# 5V.net
KiCad netlist of a schematic drawn in Altium Designer
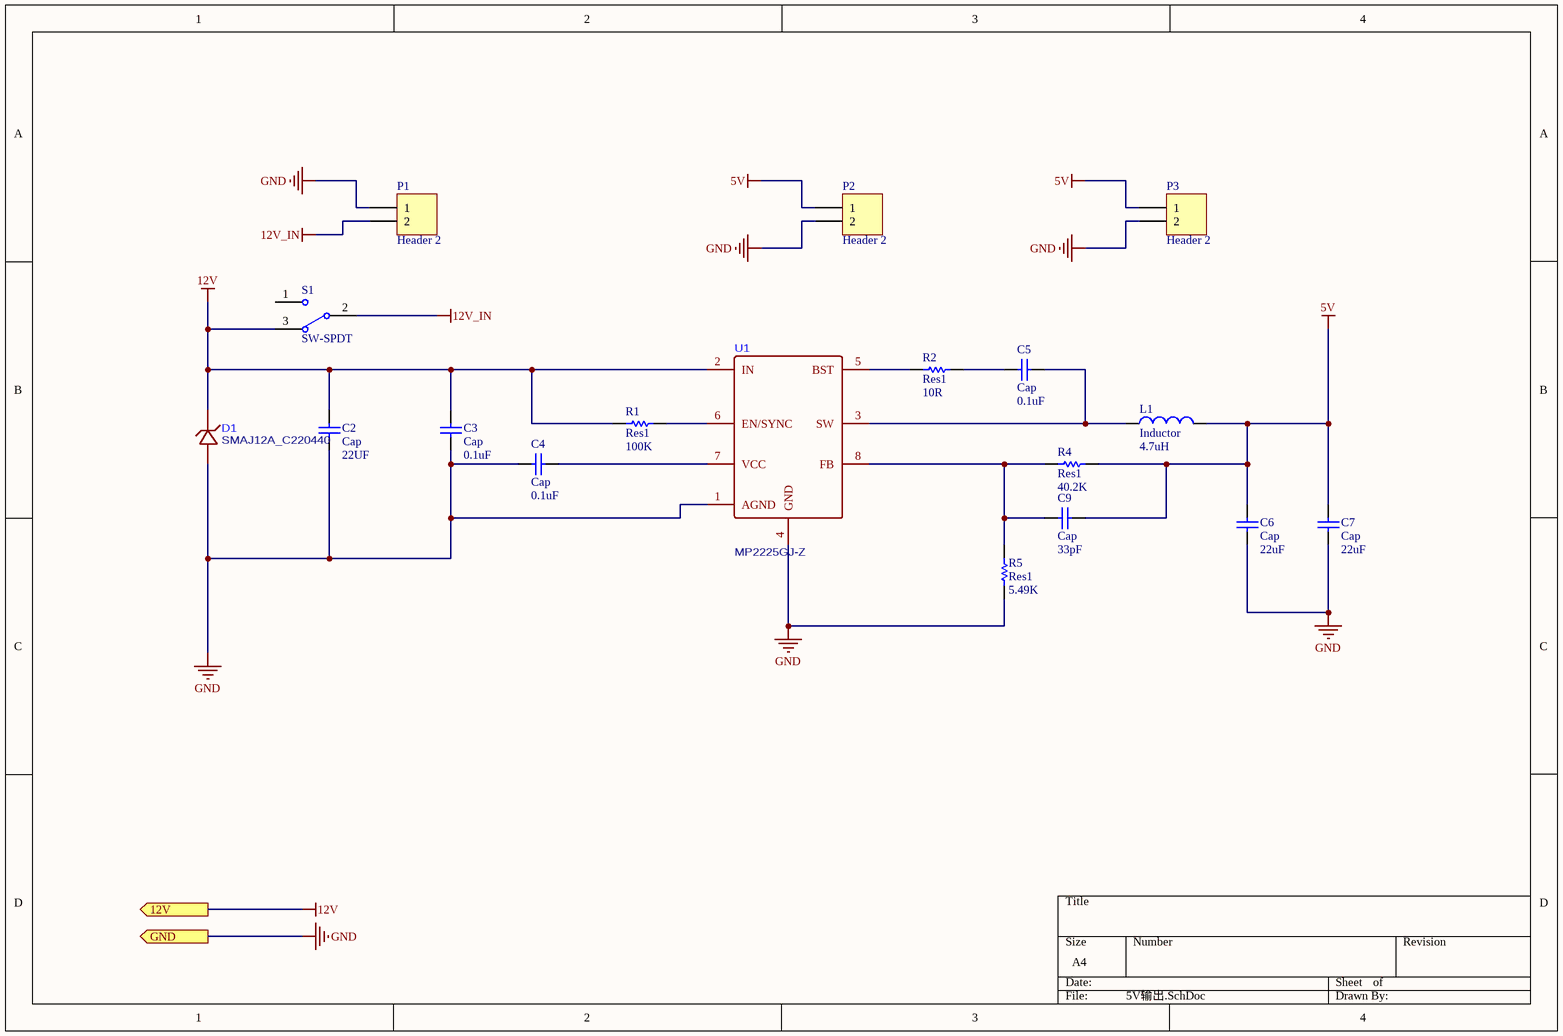
[diagram p0: 5V输出.SchDoc]

(export (version "E")
  (design (tool "Eeschema 10.0.6"))
  (components
    (comp (ref "C2")
      (value "Cap")
      (footprint "C1206")
      (description "Capacitor")
      (fields (field (name "ALTIUM_VALUE") "22UF") (field (name "PUBLISHER") "Altium Limited"))
      (libsource (lib "Miscellaneous Devices") (part "Cap"))
    )
    (comp (ref "C3")
      (value "Cap")
      (footprint "R0603")
      (description "Capacitor")
      (fields (field (name "ALTIUM_VALUE") "0.1uF") (field (name "PUBLISHER") "Altium Limited"))
      (libsource (lib "Miscellaneous Devices") (part "Cap"))
    )
    (comp (ref "C4")
      (value "Cap")
      (footprint "R0603")
      (description "Capacitor")
      (fields (field (name "ALTIUM_VALUE") "0.1uF") (field (name "PUBLISHER") "Altium Limited"))
      (libsource (lib "Miscellaneous Devices") (part "Cap"))
    )
    (comp (ref "C5")
      (value "Cap")
      (footprint "R0603")
      (description "Capacitor")
      (fields (field (name "ALTIUM_VALUE") "0.1uF") (field (name "PUBLISHER") "Altium Limited"))
      (libsource (lib "Miscellaneous Devices") (part "Cap"))
    )
    (comp (ref "C6")
      (value "Cap")
      (footprint "C0805")
      (description "Capacitor")
      (fields (field (name "ALTIUM_VALUE") "22uF") (field (name "PUBLISHER") "Altium Limited"))
      (libsource (lib "Miscellaneous Devices") (part "Cap"))
    )
    (comp (ref "C7")
      (value "Cap")
      (footprint "C0805")
      (description "Capacitor")
      (fields (field (name "ALTIUM_VALUE") "22uF") (field (name "PUBLISHER") "Altium Limited"))
      (libsource (lib "Miscellaneous Devices") (part "Cap"))
    )
    (comp (ref "C9")
      (value "Cap")
      (footprint "R0603")
      (description "Capacitor")
      (fields (field (name "ALTIUM_VALUE") "33pF") (field (name "PUBLISHER") "Altium Limited"))
      (libsource (lib "Miscellaneous Devices") (part "Cap"))
    )
    (comp (ref "D1")
      (value "SMAJ12A_C220440")
      (footprint "SMA_L4.4-W2.8-LS5.4-RD")
      (libsource (lib "SMAJ12A_C220440_2021-10-18") (part "SMAJ12A_C220440"))
    )
    (comp (ref "L1")
      (value "Inductor")
      (footprint "IND-SMD_L7.8-W7.0_MAPM0630F")
      (fields (field (name "ALTIUM_VALUE") "4.7uH") (field (name "PUBLISHER") "Altium Limited"))
      (libsource (lib "Miscellaneous Devices") (part "Inductor"))
    )
    (comp (ref "P1")
      (value "Header 2")
      (footprint "CONN-TH_XT30UPB-M")
      (description "Header, 2-Pin")
      (fields (field (name "PUBLISHER") "Altium Limited"))
      (libsource (lib "Miscellaneous Connectors") (part "Header 2"))
    )
    (comp (ref "P2")
      (value "Header 2")
      (footprint "XH2.54-2A")
      (description "Header, 2-Pin")
      (fields (field (name "PUBLISHER") "Altium Limited"))
      (libsource (lib "Miscellaneous Connectors") (part "Header 2"))
    )
    (comp (ref "P3")
      (value "Header 2")
      (footprint "XH2.54-2A")
      (description "Header, 2-Pin")
      (fields (field (name "PUBLISHER") "Altium Limited"))
      (libsource (lib "Miscellaneous Connectors") (part "Header 2"))
    )
    (comp (ref "R1")
      (value "Res1")
      (footprint "R0603")
      (description "Resistor")
      (fields (field (name "ALTIUM_VALUE") "100K") (field (name "PUBLISHER") "Altium Limited"))
      (libsource (lib "Miscellaneous Devices") (part "Res1"))
    )
    (comp (ref "R2")
      (value "Res1")
      (footprint "R0603")
      (description "Resistor")
      (fields (field (name "ALTIUM_VALUE") "10R") (field (name "PUBLISHER") "Altium Limited"))
      (libsource (lib "Miscellaneous Devices") (part "Res1"))
    )
    (comp (ref "R4")
      (value "Res1")
      (footprint "R0603")
      (description "Resistor")
      (fields (field (name "ALTIUM_VALUE") "40.2K") (field (name "PUBLISHER") "Altium Limited"))
      (libsource (lib "Miscellaneous Devices") (part "Res1"))
    )
    (comp (ref "R5")
      (value "Res1")
      (footprint "R0603")
      (description "Resistor")
      (fields (field (name "ALTIUM_VALUE") "5.49K") (field (name "PUBLISHER") "Altium Limited"))
      (libsource (lib "Miscellaneous Devices") (part "Res1"))
    )
    (comp (ref "S1")
      (value "SW-SPDT")
      (footprint "PCBComponent_1 - duplicate")
      (description "SPDT Subminiature Toggle Switch, Right Angle Mounting, Vertical Actuation")
      (fields (field (name "PUBLISHER") "Altium Limited"))
      (libsource (lib "Miscellaneous Devices") (part "SW-SPDT"))
    )
    (comp (ref "U1")
      (value "MP2225GJ-Z")
      (footprint "TSOT-23-8_L2.9-W1.6-P0.65-LS2.8-BR")
      (libsource (lib "MP2225GJ-Z_2021-10-18") (part "MP2225GJ-Z"))
    )
  )
  (nets
    (net (code "1") (name "5V") (class "Default")
      (node (ref "C6") (pin "2") (pinfunction "2_2") (pintype "passive"))
      (node (ref "C7") (pin "2") (pinfunction "2_2") (pintype "passive"))
      (node (ref "C9") (pin "2") (pinfunction "2_2") (pintype "passive"))
      (node (ref "L1") (pin "2") (pinfunction "2_2") (pintype "passive"))
      (node (ref "P2") (pin "1") (pinfunction "1_1") (pintype "passive"))
      (node (ref "P3") (pin "1") (pinfunction "1_1") (pintype "passive"))
      (node (ref "R4") (pin "2") (pinfunction "2_2") (pintype "passive"))
    )
    (net (code "2") (name "12V") (class "Default")
      (node (ref "C2") (pin "2") (pinfunction "2_2") (pintype "passive"))
      (node (ref "C3") (pin "2") (pinfunction "2_2") (pintype "passive"))
      (node (ref "D1") (pin "1") (pinfunction "1_1") (pintype "passive"))
      (node (ref "R1") (pin "1") (pinfunction "1_1") (pintype "passive"))
      (node (ref "S1") (pin "3") (pinfunction "3_3") (pintype "passive"))
      (node (ref "U1") (pin "2") (pinfunction "IN_2") (pintype "passive"))
    )
    (net (code "3") (name "12V_IN") (class "Default")
      (node (ref "P1") (pin "2") (pinfunction "2_2") (pintype "passive"))
      (node (ref "S1") (pin "2") (pinfunction "2_2") (pintype "passive"))
    )
    (net (code "4") (name "GND") (class "Default")
      (node (ref "C2") (pin "1") (pinfunction "1_1") (pintype "passive"))
      (node (ref "C3") (pin "1") (pinfunction "1_1") (pintype "passive"))
      (node (ref "C4") (pin "1") (pinfunction "1_1") (pintype "passive"))
      (node (ref "C6") (pin "1") (pinfunction "1_1") (pintype "passive"))
      (node (ref "C7") (pin "1") (pinfunction "1_1") (pintype "passive"))
      (node (ref "D1") (pin "2") (pinfunction "2_2") (pintype "passive"))
      (node (ref "P1") (pin "1") (pinfunction "1_1") (pintype "passive"))
      (node (ref "P2") (pin "2") (pinfunction "2_2") (pintype "passive"))
      (node (ref "P3") (pin "2") (pinfunction "2_2") (pintype "passive"))
      (node (ref "R5") (pin "1") (pinfunction "1_1") (pintype "passive"))
      (node (ref "U1") (pin "1") (pinfunction "AGND_1") (pintype "passive"))
      (node (ref "U1") (pin "4") (pinfunction "GND_4") (pintype "passive"))
    )
    (net (code "5") (name "Net-(C5-Pad1)") (class "Default")
      (node (ref "C5") (pin "1") (pinfunction "1_1") (pintype "passive"))
      (node (ref "R2") (pin "2") (pinfunction "2_2") (pintype "passive"))
    )
    (net (code "6") (name "Net-(U1-BST)") (class "Default")
      (node (ref "R2") (pin "1") (pinfunction "1_1") (pintype "passive"))
      (node (ref "U1") (pin "5") (pinfunction "BST_5") (pintype "passive"))
    )
    (net (code "7") (name "Net-(U1-EN{slash}SYNC)") (class "Default")
      (node (ref "R1") (pin "2") (pinfunction "2_2") (pintype "passive"))
      (node (ref "U1") (pin "6") (pinfunction "EN/SYNC_6") (pintype "passive"))
    )
    (net (code "8") (name "Net-(U1-FB)") (class "Default")
      (node (ref "C9") (pin "1") (pinfunction "1_1") (pintype "passive"))
      (node (ref "R4") (pin "1") (pinfunction "1_1") (pintype "passive"))
      (node (ref "R5") (pin "2") (pinfunction "2_2") (pintype "passive"))
      (node (ref "U1") (pin "8") (pinfunction "FB_8") (pintype "passive"))
    )
    (net (code "9") (name "Net-(U1-SW)") (class "Default")
      (node (ref "C5") (pin "2") (pinfunction "2_2") (pintype "passive"))
      (node (ref "L1") (pin "1") (pinfunction "1_1") (pintype "passive"))
      (node (ref "U1") (pin "3") (pinfunction "SW_3") (pintype "passive"))
    )
    (net (code "10") (name "Net-(U1-VCC)") (class "Default")
      (node (ref "C4") (pin "2") (pinfunction "2_2") (pintype "passive"))
      (node (ref "U1") (pin "7") (pinfunction "VCC_7") (pintype "passive"))
    )
    (net (code "11") (name "unconnected-(S1-Pad1)") (class "Default")
      (node (ref "S1") (pin "1") (pinfunction "1_1") (pintype "passive"))
    )
  )
)
